# 612_jetracer_esp32c3_030000.net
KiCad netlist of a schematic drawn in EAGLE
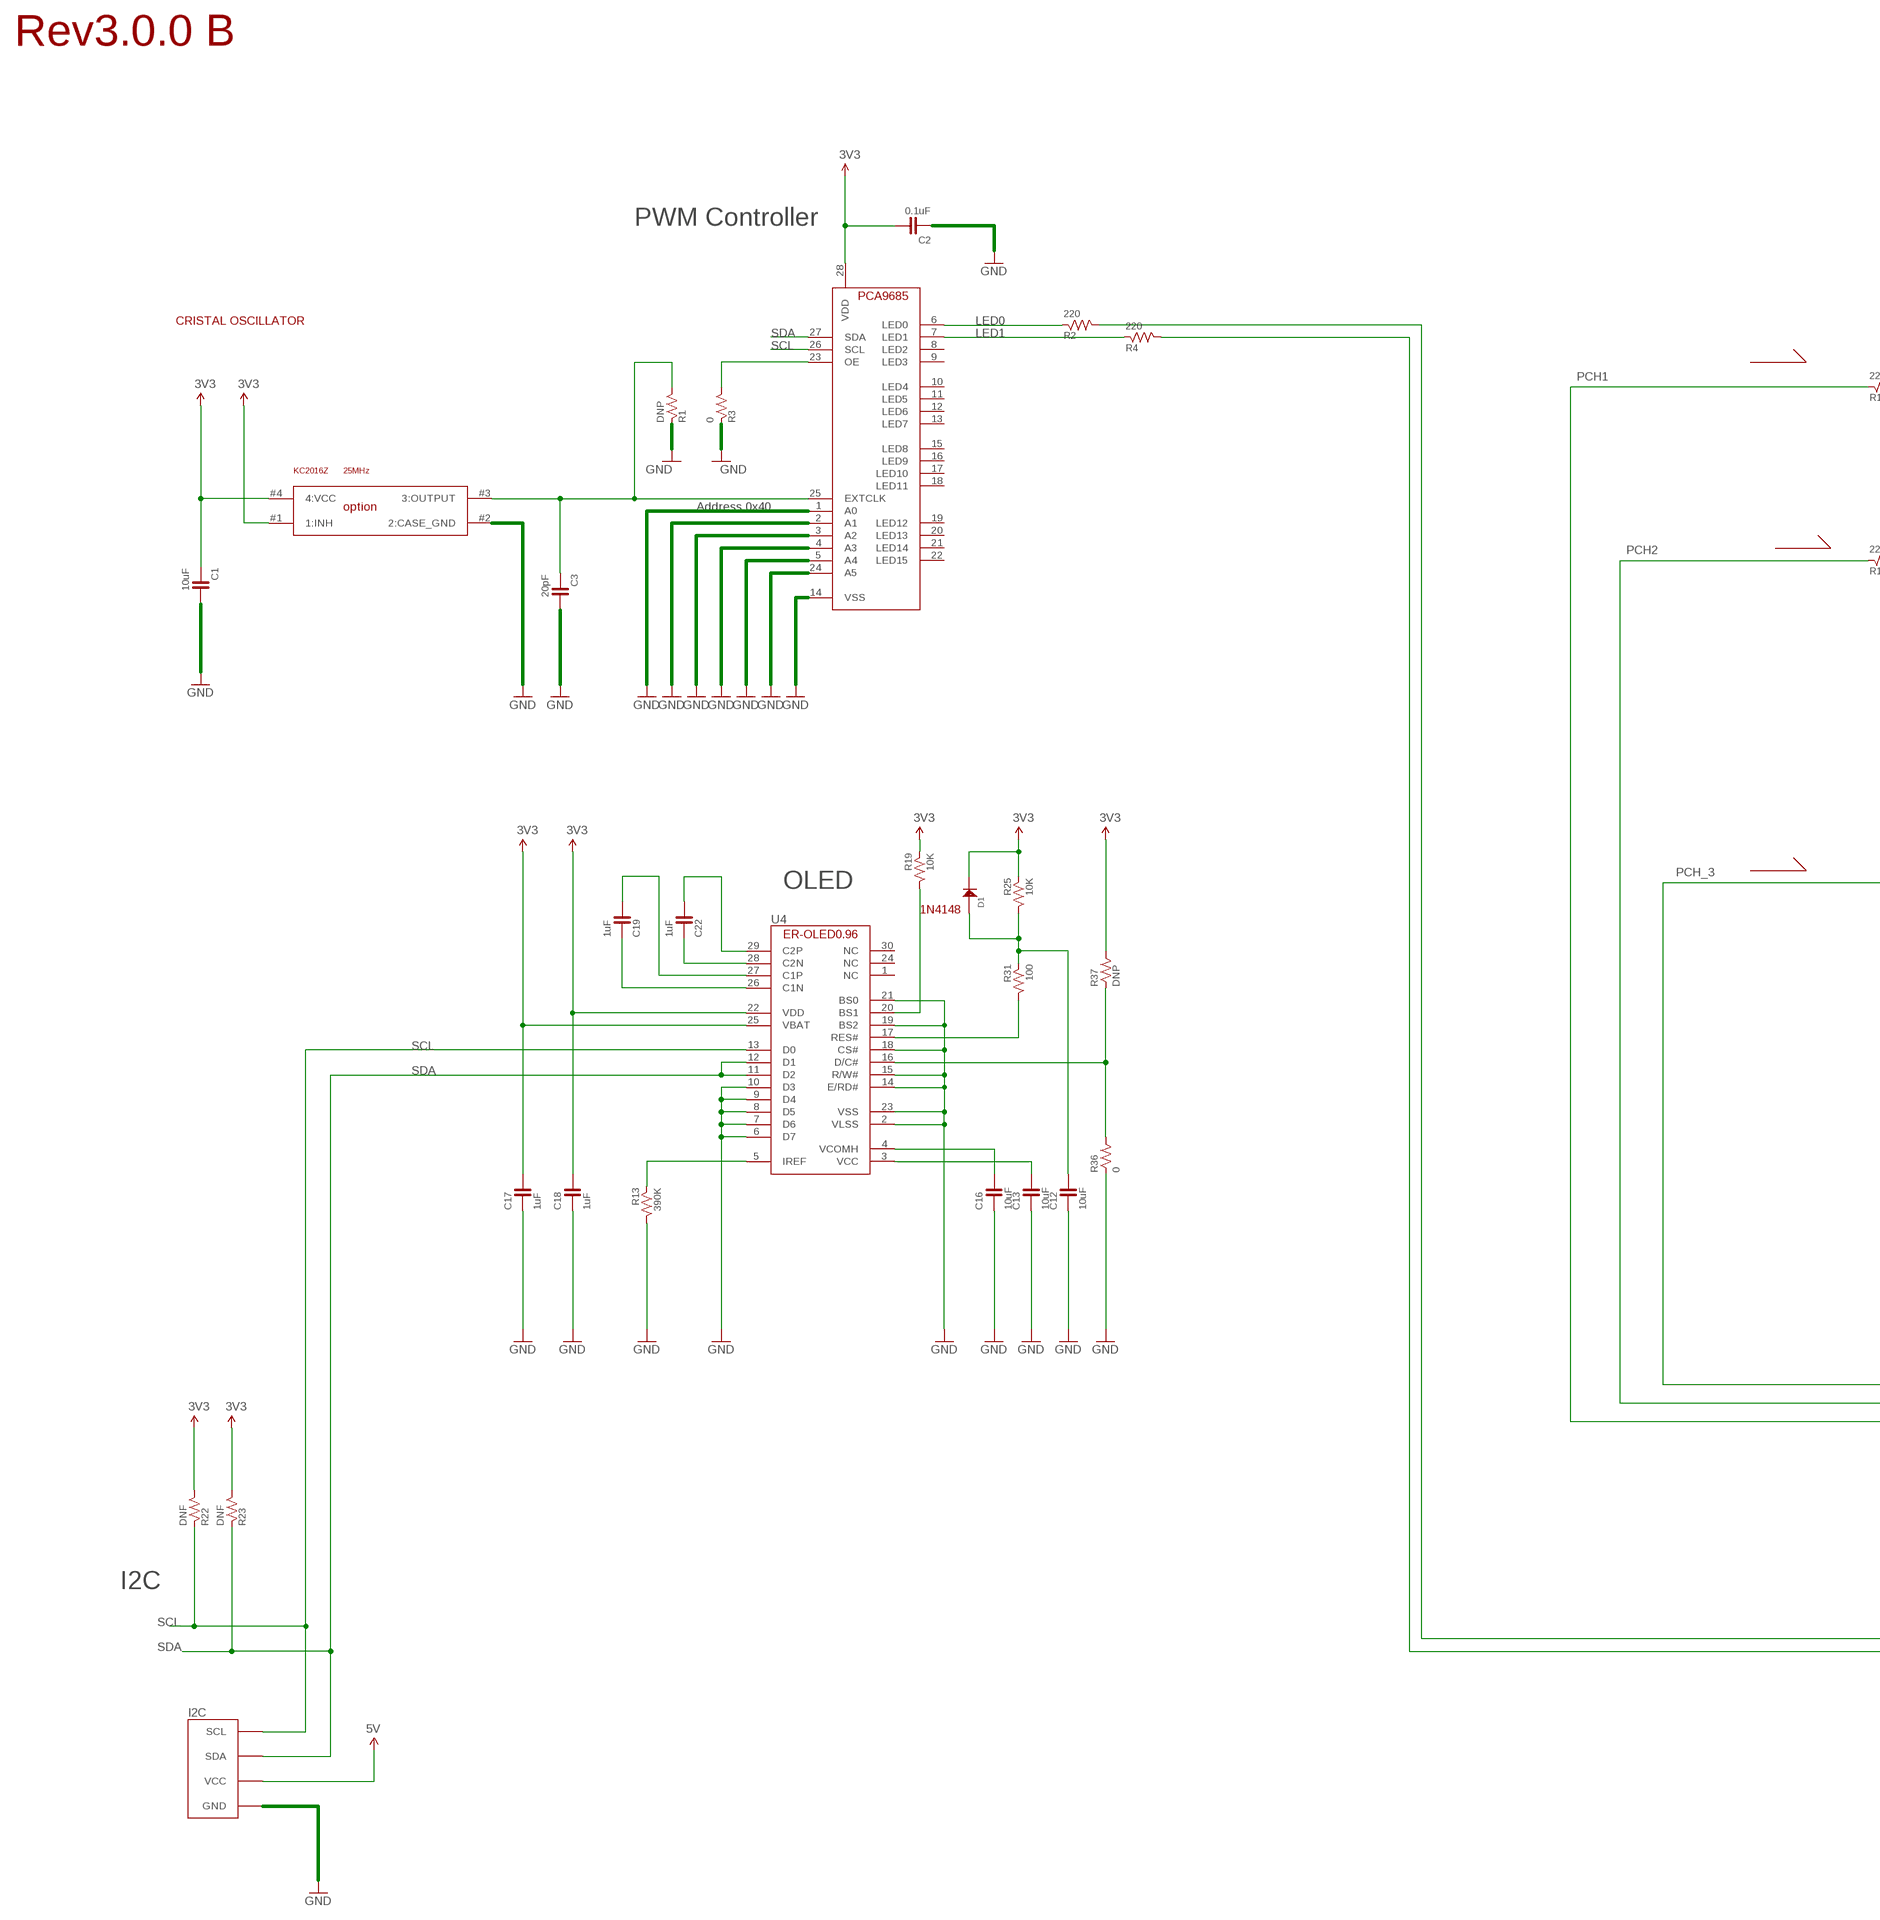
[diagram p0: schematic, sheet 1, part 1 of 3]
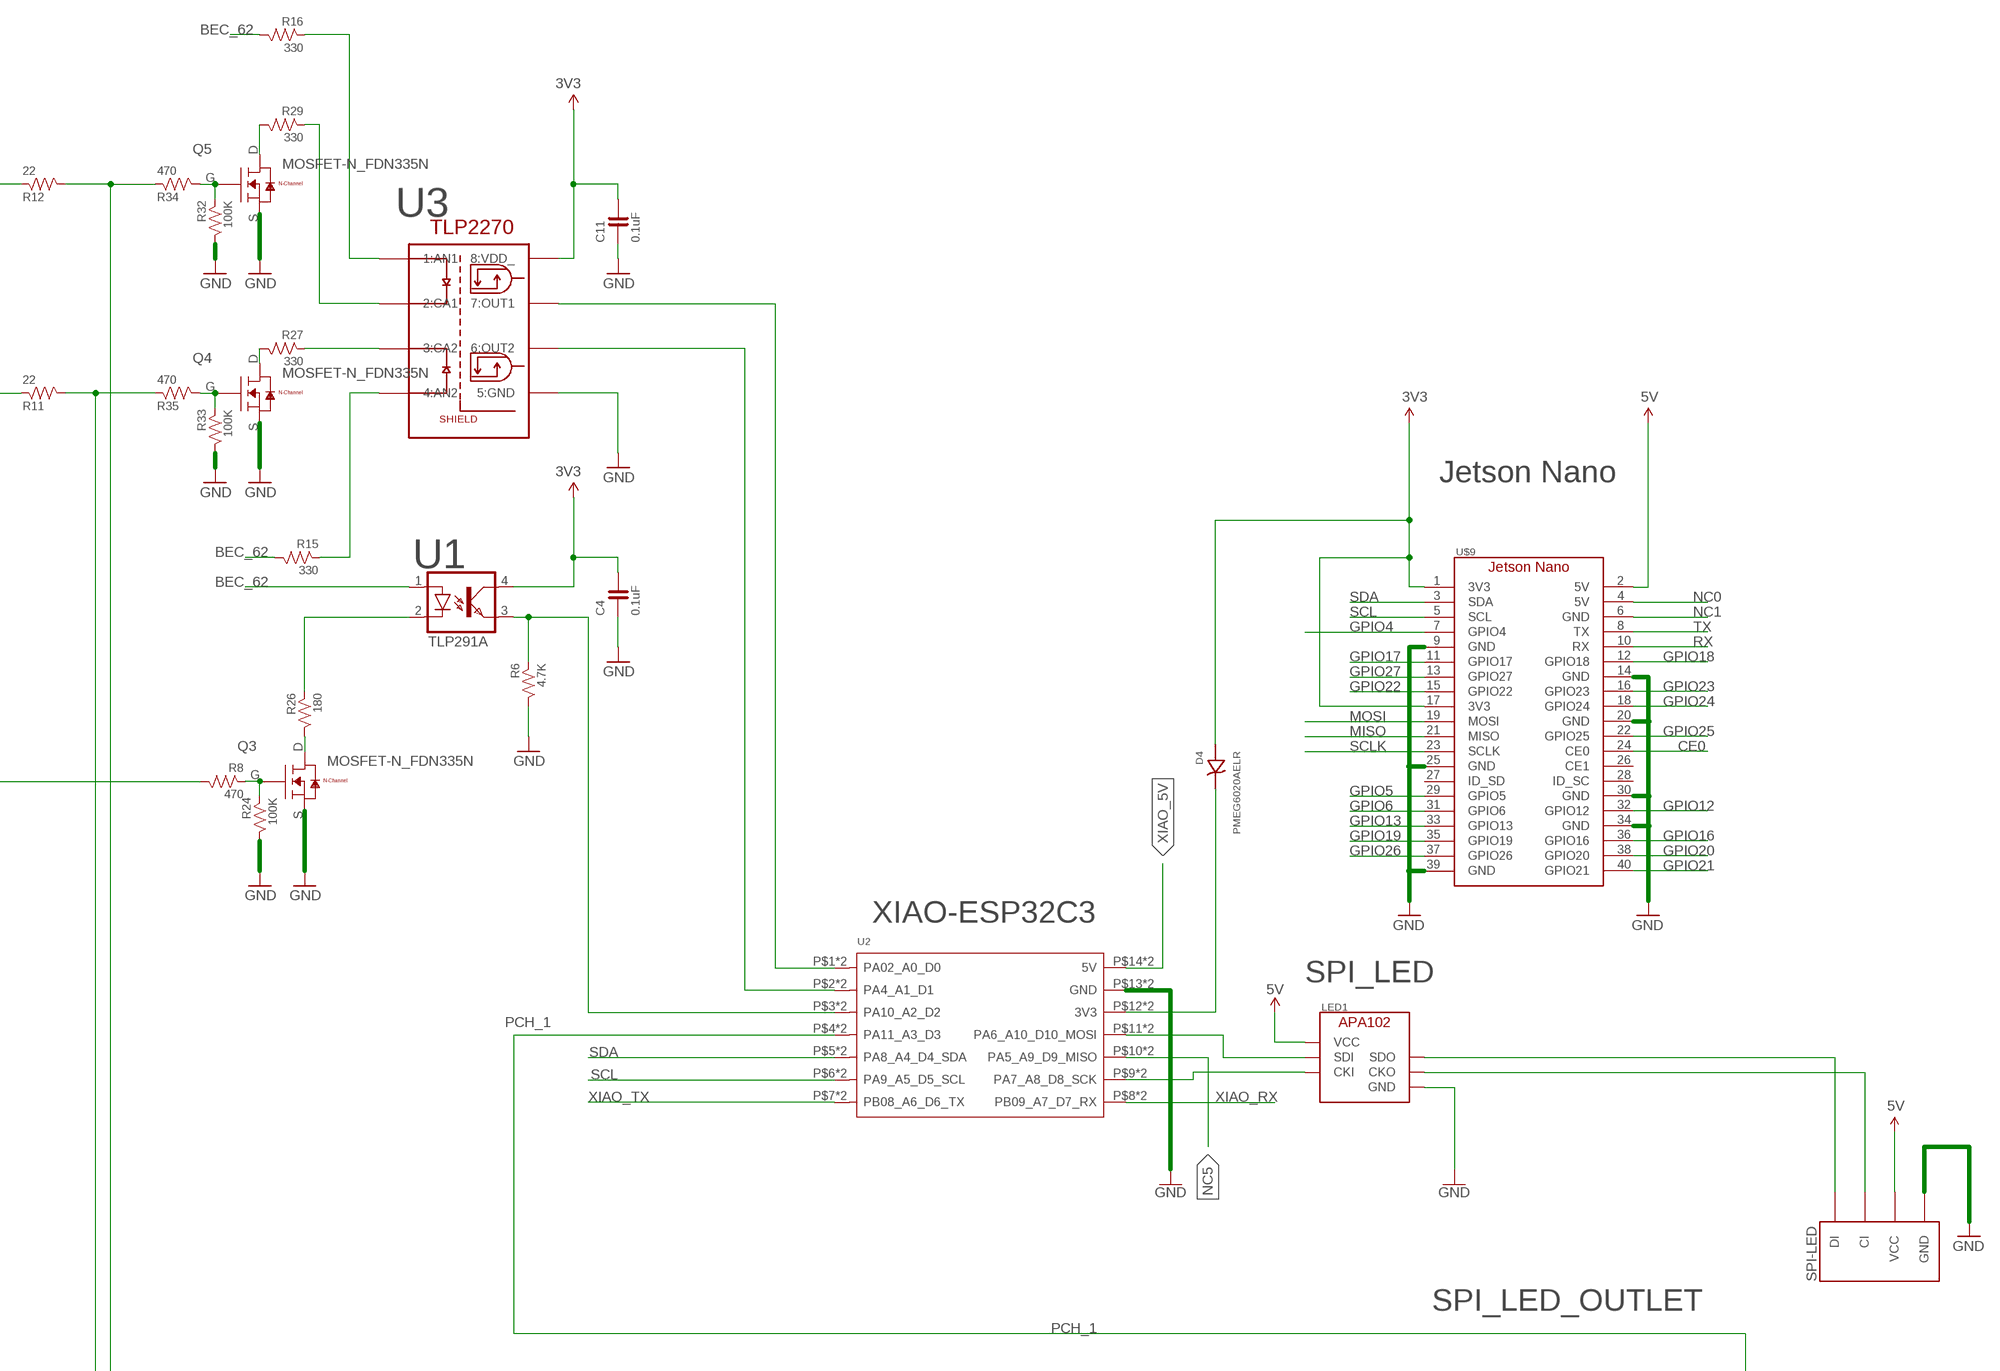
[diagram p1: schematic, sheet 1, part 2 of 3]
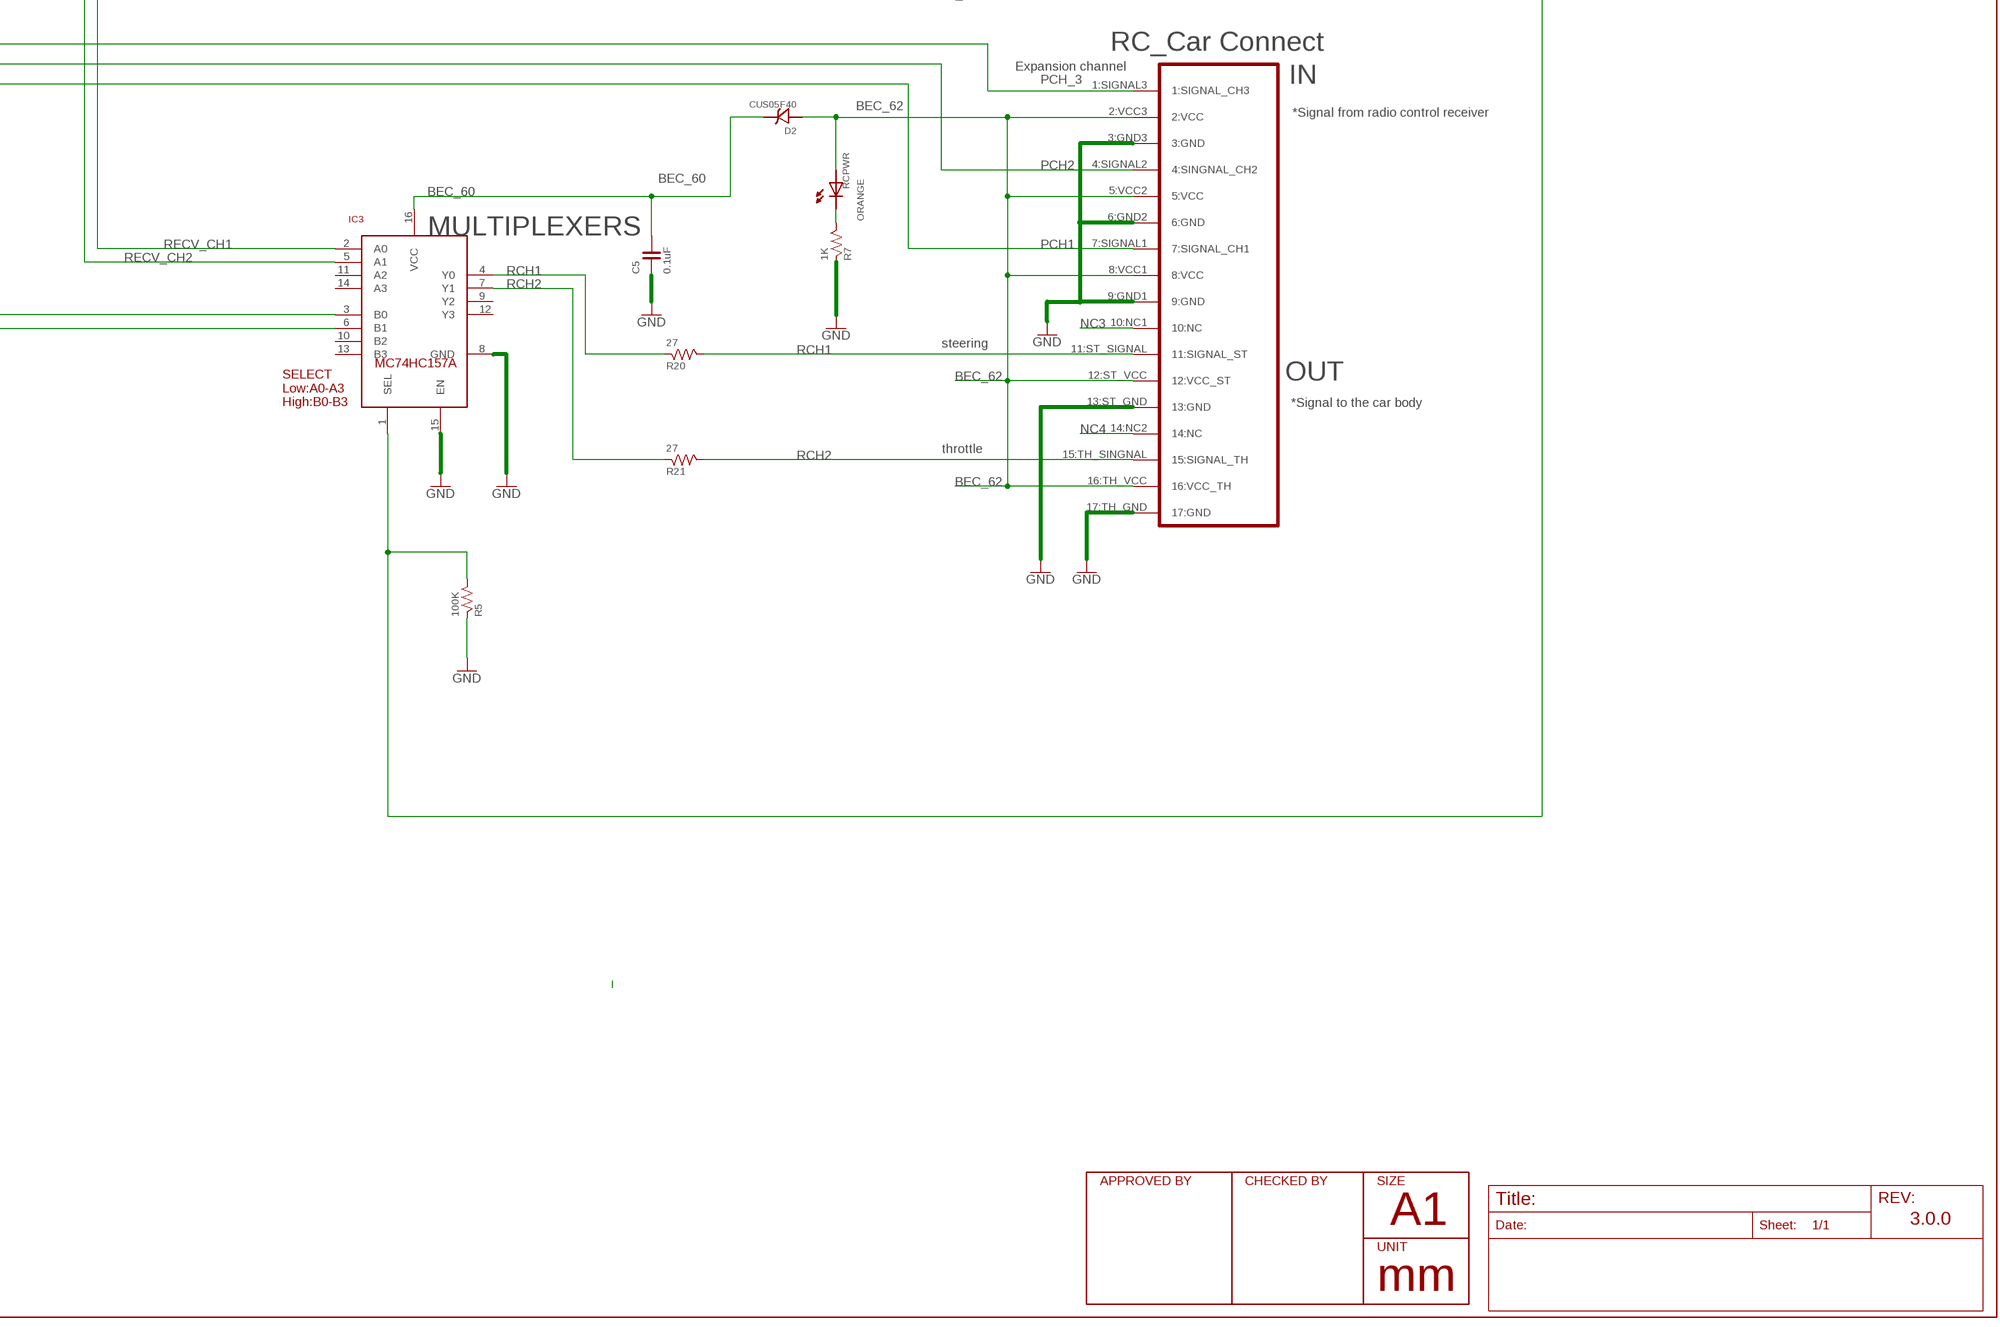
[diagram p2: schematic, sheet 1, part 3 of 3]

(export (version "E")
  (design (tool "Eeschema 10.0.6"))
  (components
    (comp (ref "C1")
      (value "10uF")
      (footprint "eagle-import:0603")
      (libsource (lib "eagle-import") (part "CAPACITOR-0603"))
    )
    (comp (ref "C2")
      (value "0.1uF")
      (footprint "eagle-import:0603")
      (libsource (lib "eagle-import") (part "CAPACITOR-0603"))
    )
    (comp (ref "C3")
      (value "20pF")
      (footprint "eagle-import:0603")
      (libsource (lib "eagle-import") (part "CAPACITOR-0603"))
    )
    (comp (ref "C4")
      (value "0.1uF")
      (footprint "eagle-import:0603")
      (libsource (lib "eagle-import") (part "CAPACITOR-0603"))
    )
    (comp (ref "C5")
      (value "0.1uF")
      (footprint "eagle-import:0603")
      (libsource (lib "eagle-import") (part "CAPACITOR-0603"))
    )
    (comp (ref "C11")
      (value "0.1uF")
      (footprint "eagle-import:0603")
      (libsource (lib "eagle-import") (part "CAPACITOR-0603"))
    )
    (comp (ref "C12")
      (value "10uF")
      (footprint "eagle-import:0603")
      (libsource (lib "eagle-import") (part "CAPACITOR-0603"))
    )
    (comp (ref "C13")
      (value "10uF")
      (footprint "eagle-import:0603")
      (libsource (lib "eagle-import") (part "CAPACITOR-0603"))
    )
    (comp (ref "C16")
      (value "10uF")
      (footprint "eagle-import:0603")
      (libsource (lib "eagle-import") (part "CAPACITOR-0603"))
    )
    (comp (ref "C17")
      (value "1uF")
      (footprint "eagle-import:0603")
      (libsource (lib "eagle-import") (part "CAPACITOR-0603"))
    )
    (comp (ref "C18")
      (value "1uF")
      (footprint "eagle-import:0603")
      (libsource (lib "eagle-import") (part "CAPACITOR-0603"))
    )
    (comp (ref "C19")
      (value "1uF")
      (footprint "eagle-import:0603")
      (libsource (lib "eagle-import") (part "CAPACITOR-0603"))
    )
    (comp (ref "C22")
      (value "1uF")
      (footprint "eagle-import:0603")
      (libsource (lib "eagle-import") (part "CAPACITOR-0603"))
    )
    (comp (ref "D1")
      (value "1N4148")
      (footprint "eagle-import:1N4148W")
      (libsource (lib "eagle-import") (part "1N4148"))
    )
    (comp (ref "D2")
      (value "CUS05F40")
      (footprint "eagle-import:CUS05F40")
      (libsource (lib "eagle-import") (part "CUS05F40"))
    )
    (comp (ref "D4")
      (value "PMEG6020AELR")
      (footprint "eagle-import:SOD123W")
      (libsource (lib "eagle-import") (part "PMEG6020AELR"))
    )
    (comp (ref "I2C")
      (value "FABO-I2C")
      (footprint "eagle-import:I2C-SM04B-PASS-1-FL")
      (libsource (lib "eagle-import") (part "FABO-I2C"))
    )
    (comp (ref "IC3")
      (value "MULTIPLEXERSMC74HC157A")
      (footprint "eagle-import:TSSOP-16")
      (libsource (lib "eagle-import") (part "MULTIPLEXERSMC74HC157A"))
    )
    (comp (ref "IC4")
      (value "PCA9685_BOTTOM")
      (footprint "eagle-import:PCA9685_BOTTOM")
      (libsource (lib "eagle-import") (part "PCA9685_BOTTOM"))
    )
    (comp (ref "LED1")
      (value "APA102_IPIXEL")
      (footprint "eagle-import:APA102_2020")
      (libsource (lib "eagle-import") (part "APA102_IPIXEL"))
    )
    (comp (ref "Q3")
      (value "MOSFET-N_FDN335N")
      (footprint "eagle-import:SUPERSOT-3")
      (libsource (lib "eagle-import") (part "MOSFET-N_FDN335N"))
    )
    (comp (ref "Q4")
      (value "MOSFET-N_FDN335N")
      (footprint "eagle-import:SUPERSOT-3")
      (libsource (lib "eagle-import") (part "MOSFET-N_FDN335N"))
    )
    (comp (ref "Q5")
      (value "MOSFET-N_FDN335N")
      (footprint "eagle-import:SUPERSOT-3")
      (libsource (lib "eagle-import") (part "MOSFET-N_FDN335N"))
    )
    (comp (ref "R1")
      (value "DNP")
      (footprint "eagle-import:0603")
      (libsource (lib "eagle-import") (part "RESISTOR-0603"))
    )
    (comp (ref "R2")
      (value "220")
      (footprint "eagle-import:0603")
      (libsource (lib "eagle-import") (part "RESISTOR-0603"))
    )
    (comp (ref "R3")
      (value "0")
      (footprint "eagle-import:0603")
      (libsource (lib "eagle-import") (part "RESISTOR-0603"))
    )
    (comp (ref "R4")
      (value "220")
      (footprint "eagle-import:0603")
      (libsource (lib "eagle-import") (part "RESISTOR-0603"))
    )
    (comp (ref "R5")
      (value "100K")
      (footprint "eagle-import:0603")
      (libsource (lib "eagle-import") (part "RESISTOR-0603"))
    )
    (comp (ref "R6")
      (value "4.7K")
      (footprint "eagle-import:0603")
      (libsource (lib "eagle-import") (part "RESISTOR-0603"))
    )
    (comp (ref "R7")
      (value "1K")
      (footprint "eagle-import:0603")
      (libsource (lib "eagle-import") (part "RESISTOR-0603"))
    )
    (comp (ref "R8")
      (value "470")
      (footprint "eagle-import:0603")
      (libsource (lib "eagle-import") (part "RESISTOR-0603"))
    )
    (comp (ref "R11")
      (value "22")
      (footprint "eagle-import:0603")
      (libsource (lib "eagle-import") (part "RESISTOR-0603"))
    )
    (comp (ref "R12")
      (value "22")
      (footprint "eagle-import:0603")
      (libsource (lib "eagle-import") (part "RESISTOR-0603"))
    )
    (comp (ref "R13")
      (value "390K")
      (footprint "eagle-import:0603")
      (libsource (lib "eagle-import") (part "RESISTOR-0603"))
    )
    (comp (ref "R15")
      (value "330")
      (footprint "eagle-import:0603")
      (libsource (lib "eagle-import") (part "RESISTOR-0603"))
    )
    (comp (ref "R16")
      (value "330")
      (footprint "eagle-import:0603")
      (libsource (lib "eagle-import") (part "RESISTOR-0603"))
    )
    (comp (ref "R19")
      (value "10K")
      (footprint "eagle-import:0603")
      (libsource (lib "eagle-import") (part "RESISTOR-0603"))
    )
    (comp (ref "R20")
      (value "27")
      (footprint "eagle-import:0603")
      (libsource (lib "eagle-import") (part "RESISTOR-0603"))
    )
    (comp (ref "R21")
      (value "27")
      (footprint "eagle-import:0603")
      (libsource (lib "eagle-import") (part "RESISTOR-0603"))
    )
    (comp (ref "R22")
      (value "DNF")
      (footprint "eagle-import:0603")
      (libsource (lib "eagle-import") (part "RESISTOR-0603"))
    )
    (comp (ref "R23")
      (value "DNF")
      (footprint "eagle-import:0603")
      (libsource (lib "eagle-import") (part "RESISTOR-0603"))
    )
    (comp (ref "R24")
      (value "100K")
      (footprint "eagle-import:0603")
      (libsource (lib "eagle-import") (part "RESISTOR-0603"))
    )
    (comp (ref "R25")
      (value "10K")
      (footprint "eagle-import:0603")
      (libsource (lib "eagle-import") (part "RESISTOR-0603"))
    )
    (comp (ref "R26")
      (value "180")
      (footprint "eagle-import:0603")
      (libsource (lib "eagle-import") (part "RESISTOR-0603"))
    )
    (comp (ref "R27")
      (value "330")
      (footprint "eagle-import:0603")
      (libsource (lib "eagle-import") (part "RESISTOR-0603"))
    )
    (comp (ref "R29")
      (value "330")
      (footprint "eagle-import:0603")
      (libsource (lib "eagle-import") (part "RESISTOR-0603"))
    )
    (comp (ref "R31")
      (value "100")
      (footprint "eagle-import:0603")
      (libsource (lib "eagle-import") (part "RESISTOR-0603"))
    )
    (comp (ref "R32")
      (value "100K")
      (footprint "eagle-import:0603")
      (libsource (lib "eagle-import") (part "RESISTOR-0603"))
    )
    (comp (ref "R33")
      (value "100K")
      (footprint "eagle-import:0603")
      (libsource (lib "eagle-import") (part "RESISTOR-0603"))
    )
    (comp (ref "R34")
      (value "470")
      (footprint "eagle-import:0603")
      (libsource (lib "eagle-import") (part "RESISTOR-0603"))
    )
    (comp (ref "R35")
      (value "470")
      (footprint "eagle-import:0603")
      (libsource (lib "eagle-import") (part "RESISTOR-0603"))
    )
    (comp (ref "R36")
      (value "0")
      (footprint "eagle-import:0805")
      (libsource (lib "eagle-import") (part "RESISTOR-0805"))
    )
    (comp (ref "R37")
      (value "DNP")
      (footprint "eagle-import:0805")
      (fields (field (name "SPICEPREFIX") "R"))
      (libsource (lib "eagle-import") (part "RESISTOR-0805"))
    )
    (comp (ref "RCPWR")
      (value "ORANGE")
      (footprint "eagle-import:0603")
      (libsource (lib "eagle-import") (part "LED-0603"))
    )
    (comp (ref "SPI-LED")
      (value "FABO-SPI-LED")
      (footprint "eagle-import:SPI-SM04B-PASS-1-FL")
      (libsource (lib "eagle-import") (part "FABO-SPI-LED"))
    )
    (comp (ref "U$1")
      (value "RC_17PIN_OUTIN")
      (footprint "eagle-import:PNHEADER_2.54_SMT_17PIN_RC_TT01_02")
      (libsource (lib "eagle-import") (part "RC_17PIN_OUTIN"))
    )
    (comp (ref "U$9")
      (value "JETSON_NANOJETSON_NANO_OVERALL")
      (footprint "eagle-import:JETSON_NANO_DEMENTION")
      (libsource (lib "eagle-import") (part "JETSON_NANOJETSON_NANO_OVERALL"))
    )
    (comp (ref "U$11")
      (value "KC2016Z")
      (footprint "eagle-import:KC2016Z")
      (libsource (lib "eagle-import") (part "KC2016Z"))
    )
    (comp (ref "U1")
      (value "TLP291A")
      (footprint "eagle-import:11-3C1")
      (libsource (lib "eagle-import") (part "TLP291A"))
    )
    (comp (ref "U2")
      (value "MOUDLE-SEEEDUINO-XIAO-ESP32C3")
      (footprint "eagle-import:MOUDLE14P-DIP")
      (libsource (lib "eagle-import") (part "MOUDLE-SEEEDUINO-XIAO-ESP32C3"))
    )
    (comp (ref "U3")
      (value "TLP2270")
      (footprint "eagle-import:TLP2270")
      (libsource (lib "eagle-import") (part "TLP2270"))
    )
    (comp (ref "U4")
      (value "ER-OLED0.96-1ER-CON30HT-1")
      (footprint "eagle-import:ER-CON30HT-1")
      (libsource (lib "eagle-import") (part "ER-OLED0.96-1ER-CON30HT-1"))
    )
  )
  (nets
    (net (code "1") (name "/BEC_60") (class "Default")
      (node (ref "C5") (pin "2") (pinfunction "2_2") (pintype "passive"))
      (node (ref "D2") (pin "C") (pinfunction "CATHODE_C") (pintype "bidirectional"))
      (node (ref "IC3") (pin "16") (pinfunction "VCC_16") (pintype "bidirectional"))
    )
    (net (code "2") (name "/BEC_62") (class "Default")
      (node (ref "D2") (pin "A") (pinfunction "ANODE_A") (pintype "bidirectional"))
      (node (ref "R15") (pin "2") (pinfunction "2_2") (pintype "bidirectional"))
      (node (ref "R16") (pin "2") (pinfunction "2_2") (pintype "bidirectional"))
      (node (ref "RCPWR") (pin "ANODE") (pinfunction "ANODE_ANODE") (pintype "passive"))
      (node (ref "U$1") (pin "12:ST_VCC") (pinfunction "12:VCC_ST_12:ST_VCC") (pintype "bidirectional"))
      (node (ref "U$1") (pin "16:TH_VCC") (pinfunction "16:VCC_TH_16:TH_VCC") (pintype "bidirectional"))
      (node (ref "U$1") (pin "2:VCC3") (pinfunction "2:VCC_2:VCC3") (pintype "bidirectional"))
      (node (ref "U$1") (pin "5:VCC2") (pinfunction "5:VCC_5:VCC2") (pintype "bidirectional"))
      (node (ref "U$1") (pin "8:VCC1") (pinfunction "8:VCC_8:VCC1") (pintype "bidirectional"))
      (node (ref "U1") (pin "1") (pinfunction "A_1") (pintype "passive"))
    )
    (net (code "3") (name "/CE0") (class "Default")
      (node (ref "U$9") (pin "24") (pinfunction "CE0_24") (pintype "bidirectional"))
    )
    (net (code "4") (name "/GPIO4") (class "Default")
      (node (ref "U$9") (pin "7") (pinfunction "GPIO4_7") (pintype "bidirectional"))
    )
    (net (code "5") (name "/GPIO5") (class "Default")
      (node (ref "U$9") (pin "29") (pinfunction "GPIO5_29") (pintype "bidirectional"))
    )
    (net (code "6") (name "/GPIO6") (class "Default")
      (node (ref "U$9") (pin "31") (pinfunction "GPIO6_31") (pintype "bidirectional"))
    )
    (net (code "7") (name "/GPIO12") (class "Default")
      (node (ref "U$9") (pin "32") (pinfunction "GPIO12_32") (pintype "bidirectional"))
    )
    (net (code "8") (name "/GPIO13") (class "Default")
      (node (ref "U$9") (pin "33") (pinfunction "GPIO13_33") (pintype "bidirectional"))
    )
    (net (code "9") (name "/GPIO16") (class "Default")
      (node (ref "U$9") (pin "36") (pinfunction "GPIO16_36") (pintype "bidirectional"))
    )
    (net (code "10") (name "/GPIO17") (class "Default")
      (node (ref "U$9") (pin "11") (pinfunction "GPIO17_11") (pintype "bidirectional"))
    )
    (net (code "11") (name "/GPIO18") (class "Default")
      (node (ref "U$9") (pin "12") (pinfunction "GPIO18_12") (pintype "bidirectional"))
    )
    (net (code "12") (name "/GPIO19") (class "Default")
      (node (ref "U$9") (pin "35") (pinfunction "GPIO19_35") (pintype "bidirectional"))
    )
    (net (code "13") (name "/GPIO20") (class "Default")
      (node (ref "U$9") (pin "38") (pinfunction "GPIO20_38") (pintype "bidirectional"))
    )
    (net (code "14") (name "/GPIO21") (class "Default")
      (node (ref "U$9") (pin "40") (pinfunction "GPIO21_40") (pintype "bidirectional"))
    )
    (net (code "15") (name "/GPIO22") (class "Default")
      (node (ref "U$9") (pin "15") (pinfunction "GPIO22_15") (pintype "bidirectional"))
    )
    (net (code "16") (name "/GPIO23") (class "Default")
      (node (ref "U$9") (pin "16") (pinfunction "GPIO23_16") (pintype "bidirectional"))
    )
    (net (code "17") (name "/GPIO24") (class "Default")
      (node (ref "U$9") (pin "18") (pinfunction "GPIO24_18") (pintype "bidirectional"))
    )
    (net (code "18") (name "/GPIO25") (class "Default")
      (node (ref "U$9") (pin "22") (pinfunction "GPIO25_22") (pintype "bidirectional"))
    )
    (net (code "19") (name "/GPIO26") (class "Default")
      (node (ref "U$9") (pin "37") (pinfunction "GPIO26_37") (pintype "bidirectional"))
    )
    (net (code "20") (name "/GPIO27") (class "Default")
      (node (ref "U$9") (pin "13") (pinfunction "GPIO27_13") (pintype "bidirectional"))
    )
    (net (code "21") (name "/LED0") (class "Default")
      (node (ref "IC4") (pin "6") (pinfunction "LED0_6") (pintype "bidirectional"))
      (node (ref "R2") (pin "1") (pinfunction "1_1") (pintype "bidirectional"))
    )
    (net (code "22") (name "/LED1") (class "Default")
      (node (ref "IC4") (pin "7") (pinfunction "LED1_7") (pintype "bidirectional"))
      (node (ref "R4") (pin "1") (pinfunction "1_1") (pintype "bidirectional"))
    )
    (net (code "23") (name "/MISO") (class "Default")
      (node (ref "U$9") (pin "21") (pinfunction "MISO_21") (pintype "bidirectional"))
    )
    (net (code "24") (name "/MOSI") (class "Default")
      (node (ref "U$9") (pin "19") (pinfunction "MOSI_19") (pintype "bidirectional"))
    )
    (net (code "25") (name "/NC0") (class "Default")
      (node (ref "U$9") (pin "4") (pinfunction "5V_4") (pintype "bidirectional"))
    )
    (net (code "26") (name "/NC1") (class "Default")
      (node (ref "U$9") (pin "6") (pinfunction "GND_6") (pintype "bidirectional"))
    )
    (net (code "27") (name "/NC3") (class "Default")
      (node (ref "U$1") (pin "10:NC1") (pinfunction "10:NC_10:NC1") (pintype "bidirectional"))
    )
    (net (code "28") (name "/NC4") (class "Default")
      (node (ref "U$1") (pin "14:NC2") (pinfunction "14:NC_14:NC2") (pintype "bidirectional"))
    )
    (net (code "29") (name "/PCH1") (class "Default")
      (node (ref "R12") (pin "1") (pinfunction "1_1") (pintype "bidirectional"))
      (node (ref "U$1") (pin "7:SIGNAL1") (pinfunction "7:SIGNAL_CH1_7:SIGNAL1") (pintype "bidirectional"))
    )
    (net (code "30") (name "/PCH2") (class "Default")
      (node (ref "R11") (pin "1") (pinfunction "1_1") (pintype "bidirectional"))
      (node (ref "U$1") (pin "4:SIGNAL2") (pinfunction "4:SINGNAL_CH2_4:SIGNAL2") (pintype "bidirectional"))
    )
    (net (code "31") (name "/PCH_1") (class "Default")
      (node (ref "IC3") (pin "1") (pinfunction "SEL_1") (pintype "bidirectional"))
      (node (ref "R5") (pin "2") (pinfunction "2_2") (pintype "bidirectional"))
      (node (ref "U2") (pin "P$18") (pinfunction "PA11_A3_D3_P$18") (pintype "bidirectional"))
      (node (ref "U2") (pin "P$4") (pinfunction "PA11_A3_D3_P$4") (pintype "bidirectional"))
    )
    (net (code "32") (name "/PCH_3") (class "Default")
      (node (ref "R8") (pin "2") (pinfunction "2_2") (pintype "bidirectional"))
      (node (ref "U$1") (pin "1:SIGNAL3") (pinfunction "1:SIGNAL_CH3_1:SIGNAL3") (pintype "bidirectional"))
    )
    (net (code "33") (name "/RCH1") (class "Default")
      (node (ref "IC3") (pin "4") (pinfunction "Y0_4") (pintype "bidirectional"))
      (node (ref "R20") (pin "1") (pinfunction "1_1") (pintype "bidirectional"))
    )
    (net (code "34") (name "/RCH2") (class "Default")
      (node (ref "IC3") (pin "7") (pinfunction "Y1_7") (pintype "bidirectional"))
      (node (ref "R21") (pin "1") (pinfunction "1_1") (pintype "bidirectional"))
    )
    (net (code "35") (name "/RECV_CH1") (class "Default")
      (node (ref "IC3") (pin "2") (pinfunction "A0_2") (pintype "bidirectional"))
      (node (ref "R12") (pin "2") (pinfunction "2_2") (pintype "bidirectional"))
      (node (ref "R34") (pin "1") (pinfunction "1_1") (pintype "bidirectional"))
    )
    (net (code "36") (name "/RECV_CH2") (class "Default")
      (node (ref "IC3") (pin "5") (pinfunction "A1_5") (pintype "bidirectional"))
      (node (ref "R11") (pin "2") (pinfunction "2_2") (pintype "bidirectional"))
      (node (ref "R35") (pin "1") (pinfunction "1_1") (pintype "bidirectional"))
    )
    (net (code "37") (name "/RX") (class "Default")
      (node (ref "U$9") (pin "10") (pinfunction "RX_10") (pintype "bidirectional"))
    )
    (net (code "38") (name "/SCL") (class "Default")
      (node (ref "I2C") (pin "SCL") (pinfunction "SCL_SCL") (pintype "bidirectional"))
      (node (ref "IC4") (pin "26") (pinfunction "SCL_26") (pintype "bidirectional"))
      (node (ref "R22") (pin "1") (pinfunction "1_1") (pintype "bidirectional"))
      (node (ref "U$9") (pin "5") (pinfunction "SCL_5") (pintype "bidirectional"))
      (node (ref "U2") (pin "P$20") (pinfunction "PA9_A5_D5_SCL_P$20") (pintype "bidirectional"))
      (node (ref "U2") (pin "P$6") (pinfunction "PA9_A5_D5_SCL_P$6") (pintype "bidirectional"))
      (node (ref "U4") (pin "13") (pinfunction "D0_13") (pintype "bidirectional"))
    )
    (net (code "39") (name "/SCLK") (class "Default")
      (node (ref "U$9") (pin "23") (pinfunction "SCLK_23") (pintype "bidirectional"))
    )
    (net (code "40") (name "/SDA") (class "Default")
      (node (ref "I2C") (pin "SDA") (pinfunction "SDA_SDA") (pintype "bidirectional"))
      (node (ref "IC4") (pin "27") (pinfunction "SDA_27") (pintype "bidirectional"))
      (node (ref "R23") (pin "1") (pinfunction "1_1") (pintype "bidirectional"))
      (node (ref "U$9") (pin "3") (pinfunction "SDA_3") (pintype "bidirectional"))
      (node (ref "U2") (pin "P$19") (pinfunction "PA8_A4_D4_SDA_P$19") (pintype "bidirectional"))
      (node (ref "U2") (pin "P$5") (pinfunction "PA8_A4_D4_SDA_P$5") (pintype "bidirectional"))
      (node (ref "U4") (pin "11") (pinfunction "D2_11") (pintype "bidirectional"))
      (node (ref "U4") (pin "12") (pinfunction "D1_12") (pintype "bidirectional"))
    )
    (net (code "41") (name "/TX") (class "Default")
      (node (ref "U$9") (pin "8") (pinfunction "TX_8") (pintype "bidirectional"))
    )
    (net (code "42") (name "/XIAO_RX") (class "Default")
      (node (ref "U2") (pin "P$22") (pinfunction "PB09_A7_D7_RX_P$22") (pintype "bidirectional"))
      (node (ref "U2") (pin "P$8") (pinfunction "PB09_A7_D7_RX_P$8") (pintype "bidirectional"))
    )
    (net (code "43") (name "/XIAO_TX") (class "Default")
      (node (ref "U2") (pin "P$21") (pinfunction "PB08_A6_D6_TX_P$21") (pintype "bidirectional"))
      (node (ref "U2") (pin "P$7") (pinfunction "PB08_A6_D6_TX_P$7") (pintype "bidirectional"))
    )
    (net (code "44") (name "3V3") (class "Default")
      (node (ref "C1") (pin "1") (pinfunction "1_1") (pintype "passive"))
      (node (ref "C11") (pin "2") (pinfunction "2_2") (pintype "passive"))
      (node (ref "C17") (pin "2") (pinfunction "2_2") (pintype "passive"))
      (node (ref "C18") (pin "2") (pinfunction "2_2") (pintype "passive"))
      (node (ref "C2") (pin "2") (pinfunction "2_2") (pintype "passive"))
      (node (ref "C4") (pin "2") (pinfunction "2_2") (pintype "passive"))
      (node (ref "D1") (pin "CATHODE") (pinfunction "CATHODE_CATHODE") (pintype "bidirectional"))
      (node (ref "D4") (pin "2") (pinfunction "ANODE_2") (pintype "bidirectional"))
      (node (ref "IC4") (pin "28") (pinfunction "VDD_28") (pintype "bidirectional"))
      (node (ref "R19") (pin "1") (pinfunction "1_1") (pintype "bidirectional"))
      (node (ref "R22") (pin "2") (pinfunction "2_2") (pintype "bidirectional"))
      (node (ref "R23") (pin "2") (pinfunction "2_2") (pintype "bidirectional"))
      (node (ref "R25") (pin "1") (pinfunction "1_1") (pintype "bidirectional"))
      (node (ref "R37") (pin "2") (pinfunction "2_2") (pintype "bidirectional"))
      (node (ref "U$11") (pin "#1") (pinfunction "1:INH_#1") (pintype "bidirectional"))
      (node (ref "U$11") (pin "#4") (pinfunction "4:VCC_#4") (pintype "bidirectional"))
      (node (ref "U$9") (pin "1") (pinfunction "3V3_1") (pintype "bidirectional"))
      (node (ref "U$9") (pin "17") (pinfunction "3V3_17") (pintype "bidirectional"))
      (node (ref "U1") (pin "4") (pinfunction "COL_4") (pintype "passive"))
      (node (ref "U3") (pin "8") (pinfunction "8:VDD__8") (pintype "bidirectional"))
      (node (ref "U4") (pin "22") (pinfunction "VDD_22") (pintype "bidirectional"))
      (node (ref "U4") (pin "25") (pinfunction "VBAT_25") (pintype "bidirectional"))
    )
    (net (code "45") (name "5V") (class "Default")
      (node (ref "I2C") (pin "5V") (pinfunction "VCC_5V") (pintype "bidirectional"))
      (node (ref "LED1") (pin "VCC") (pinfunction "VCC_VCC") (pintype "bidirectional"))
      (node (ref "SPI-LED") (pin "5V") (pinfunction "VCC_5V") (pintype "bidirectional"))
      (node (ref "U$9") (pin "2") (pinfunction "5V_2") (pintype "bidirectional"))
    )
    (net (code "46") (name "GND") (class "Default")
      (node (ref "C1") (pin "2") (pinfunction "2_2") (pintype "passive"))
      (node (ref "C11") (pin "1") (pinfunction "1_1") (pintype "passive"))
      (node (ref "C12") (pin "1") (pinfunction "1_1") (pintype "passive"))
      (node (ref "C13") (pin "1") (pinfunction "1_1") (pintype "passive"))
      (node (ref "C16") (pin "1") (pinfunction "1_1") (pintype "passive"))
      (node (ref "C17") (pin "1") (pinfunction "1_1") (pintype "passive"))
      (node (ref "C18") (pin "1") (pinfunction "1_1") (pintype "passive"))
      (node (ref "C2") (pin "1") (pinfunction "1_1") (pintype "passive"))
      (node (ref "C3") (pin "2") (pinfunction "2_2") (pintype "passive"))
      (node (ref "C4") (pin "1") (pinfunction "1_1") (pintype "passive"))
      (node (ref "C5") (pin "1") (pinfunction "1_1") (pintype "passive"))
      (node (ref "I2C") (pin "GND") (pinfunction "GND_GND") (pintype "bidirectional"))
      (node (ref "IC3") (pin "15") (pinfunction "EN_15") (pintype "bidirectional"))
      (node (ref "IC3") (pin "8") (pinfunction "GND_8") (pintype "bidirectional"))
      (node (ref "IC4") (pin "1") (pinfunction "A0_1") (pintype "bidirectional"))
      (node (ref "IC4") (pin "14") (pinfunction "VSS_14") (pintype "bidirectional"))
      (node (ref "IC4") (pin "2") (pinfunction "A1_2") (pintype "bidirectional"))
      (node (ref "IC4") (pin "24") (pinfunction "A5_24") (pintype "bidirectional"))
      (node (ref "IC4") (pin "3") (pinfunction "A2_3") (pintype "bidirectional"))
      (node (ref "IC4") (pin "4") (pinfunction "A3_4") (pintype "bidirectional"))
      (node (ref "IC4") (pin "5") (pinfunction "A4_5") (pintype "bidirectional"))
      (node (ref "LED1") (pin "GND") (pinfunction "GND_GND") (pintype "bidirectional"))
      (node (ref "Q3") (pin "S") (pinfunction "S_S") (pintype "passive"))
      (node (ref "Q4") (pin "S") (pinfunction "S_S") (pintype "passive"))
      (node (ref "Q5") (pin "S") (pinfunction "S_S") (pintype "passive"))
      (node (ref "R1") (pin "1") (pinfunction "1_1") (pintype "bidirectional"))
      (node (ref "R13") (pin "2") (pinfunction "2_2") (pintype "bidirectional"))
      (node (ref "R24") (pin "2") (pinfunction "2_2") (pintype "bidirectional"))
      (node (ref "R3") (pin "1") (pinfunction "1_1") (pintype "bidirectional"))
      (node (ref "R32") (pin "2") (pinfunction "2_2") (pintype "bidirectional"))
      (node (ref "R33") (pin "2") (pinfunction "2_2") (pintype "bidirectional"))
      (node (ref "R36") (pin "1") (pinfunction "1_1") (pintype "bidirectional"))
      (node (ref "R5") (pin "1") (pinfunction "1_1") (pintype "bidirectional"))
      (node (ref "R6") (pin "2") (pinfunction "2_2") (pintype "bidirectional"))
      (node (ref "R7") (pin "1") (pinfunction "1_1") (pintype "bidirectional"))
      (node (ref "SPI-LED") (pin "GND") (pinfunction "GND_GND") (pintype "bidirectional"))
      (node (ref "U$1") (pin "13:ST_GND") (pinfunction "13:GND_13:ST_GND") (pintype "bidirectional"))
      (node (ref "U$1") (pin "17:TH_GND") (pinfunction "17:GND_17:TH_GND") (pintype "bidirectional"))
      (node (ref "U$1") (pin "3:GND3") (pinfunction "3:GND_3:GND3") (pintype "bidirectional"))
      (node (ref "U$1") (pin "6:GND2") (pinfunction "6:GND_6:GND2") (pintype "bidirectional"))
      (node (ref "U$1") (pin "9:GND1") (pinfunction "9:GND_9:GND1") (pintype "bidirectional"))
      (node (ref "U$11") (pin "#2") (pinfunction "2:CASE_GND_#2") (pintype "bidirectional"))
      (node (ref "U$9") (pin "14") (pinfunction "GND_14") (pintype "bidirectional"))
      (node (ref "U$9") (pin "20") (pinfunction "GND_20") (pintype "bidirectional"))
      (node (ref "U$9") (pin "25") (pinfunction "GND_25") (pintype "bidirectional"))
      (node (ref "U$9") (pin "30") (pinfunction "GND_30") (pintype "bidirectional"))
      (node (ref "U$9") (pin "34") (pinfunction "GND_34") (pintype "bidirectional"))
      (node (ref "U$9") (pin "39") (pinfunction "GND_39") (pintype "bidirectional"))
      (node (ref "U$9") (pin "9") (pinfunction "GND_9") (pintype "bidirectional"))
      (node (ref "U2") (pin "P$13") (pinfunction "GND_P$13") (pintype "bidirectional"))
      (node (ref "U2") (pin "P$27") (pinfunction "GND_P$27") (pintype "bidirectional"))
      (node (ref "U3") (pin "5") (pinfunction "5:GND_5") (pintype "bidirectional"))
      (node (ref "U4") (pin "10") (pinfunction "D3_10") (pintype "bidirectional"))
      (node (ref "U4") (pin "14") (pinfunction "E/RD#_14") (pintype "bidirectional"))
      (node (ref "U4") (pin "15") (pinfunction "R/W#_15") (pintype "bidirectional"))
      (node (ref "U4") (pin "18") (pinfunction "CS#_18") (pintype "bidirectional"))
      (node (ref "U4") (pin "19") (pinfunction "BS2_19") (pintype "bidirectional"))
      (node (ref "U4") (pin "2") (pinfunction "VLSS_2") (pintype "bidirectional"))
      (node (ref "U4") (pin "21") (pinfunction "BS0_21") (pintype "bidirectional"))
      (node (ref "U4") (pin "23") (pinfunction "VSS_23") (pintype "bidirectional"))
      (node (ref "U4") (pin "6") (pinfunction "D7_6") (pintype "bidirectional"))
      (node (ref "U4") (pin "7") (pinfunction "D6_7") (pintype "bidirectional"))
      (node (ref "U4") (pin "8") (pinfunction "D5_8") (pintype "bidirectional"))
      (node (ref "U4") (pin "9") (pinfunction "D4_9") (pintype "bidirectional"))
    )
    (net (code "47") (name "NC5") (class "Default")
      (node (ref "U2") (pin "P$10") (pinfunction "PA5_A9_D9_MISO_P$10") (pintype "bidirectional"))
      (node (ref "U2") (pin "P$24") (pinfunction "PA5_A9_D9_MISO_P$24") (pintype "bidirectional"))
    )
    (net (code "48") (name "Net-(C12-Pad2)") (class "Default")
      (node (ref "C12") (pin "2") (pinfunction "2_2") (pintype "passive"))
      (node (ref "D1") (pin "ANODE") (pinfunction "ANODE_ANODE") (pintype "bidirectional"))
      (node (ref "R25") (pin "2") (pinfunction "2_2") (pintype "bidirectional"))
      (node (ref "R31") (pin "1") (pinfunction "1_1") (pintype "bidirectional"))
    )
    (net (code "49") (name "Net-(D4-CATHODE)") (class "Default")
      (node (ref "D4") (pin "1") (pinfunction "CATHODE_1") (pintype "bidirectional"))
      (node (ref "U2") (pin "P$12") (pinfunction "3V3_P$12") (pintype "bidirectional"))
      (node (ref "U2") (pin "P$26") (pinfunction "3V3_P$26") (pintype "bidirectional"))
    )
    (net (code "50") (name "Net-(IC3-B0)") (class "Default")
      (node (ref "IC3") (pin "3") (pinfunction "B0_3") (pintype "bidirectional"))
      (node (ref "R2") (pin "2") (pinfunction "2_2") (pintype "bidirectional"))
    )
    (net (code "51") (name "Net-(IC3-B1)") (class "Default")
      (node (ref "IC3") (pin "6") (pinfunction "B1_6") (pintype "bidirectional"))
      (node (ref "R4") (pin "2") (pinfunction "2_2") (pintype "bidirectional"))
    )
    (net (code "52") (name "Net-(IC4-EXTCLK)") (class "Default")
      (node (ref "C3") (pin "1") (pinfunction "1_1") (pintype "passive"))
      (node (ref "IC4") (pin "25") (pinfunction "EXTCLK_25") (pintype "bidirectional"))
      (node (ref "R1") (pin "2") (pinfunction "2_2") (pintype "bidirectional"))
      (node (ref "U$11") (pin "#3") (pinfunction "3:OUTPUT_#3") (pintype "bidirectional"))
    )
    (net (code "53") (name "Net-(IC4-OE)") (class "Default")
      (node (ref "IC4") (pin "23") (pinfunction "OE_23") (pintype "bidirectional"))
      (node (ref "R3") (pin "2") (pinfunction "2_2") (pintype "bidirectional"))
    )
    (net (code "54") (name "Net-(LED1-PadCKI)") (class "Default")
      (node (ref "LED1") (pin "CKI") (pinfunction "CKI_CKI") (pintype "bidirectional"))
      (node (ref "U2") (pin "P$23") (pinfunction "PA7_A8_D8_SCK_P$23") (pintype "bidirectional"))
      (node (ref "U2") (pin "P$9") (pinfunction "PA7_A8_D8_SCK_P$9") (pintype "bidirectional"))
    )
    (net (code "55") (name "Net-(LED1-PadCKO)") (class "Default")
      (node (ref "LED1") (pin "CKO") (pinfunction "CKO_CKO") (pintype "bidirectional"))
      (node (ref "SPI-LED") (pin "CI") (pinfunction "CI_CI") (pintype "bidirectional"))
    )
    (net (code "56") (name "Net-(LED1-PadSDI)") (class "Default")
      (node (ref "LED1") (pin "SDI") (pinfunction "SDI_SDI") (pintype "bidirectional"))
      (node (ref "U2") (pin "P$11") (pinfunction "PA6_A10_D10_MOSI_P$11") (pintype "bidirectional"))
      (node (ref "U2") (pin "P$25") (pinfunction "PA6_A10_D10_MOSI_P$25") (pintype "bidirectional"))
    )
    (net (code "57") (name "Net-(LED1-PadSDO)") (class "Default")
      (node (ref "LED1") (pin "SDO") (pinfunction "SDO_SDO") (pintype "bidirectional"))
      (node (ref "SPI-LED") (pin "DI") (pinfunction "DI_DI") (pintype "bidirectional"))
    )
    (net (code "58") (name "Net-(Q3-PadD)") (class "Default")
      (node (ref "Q3") (pin "D") (pinfunction "D_D") (pintype "passive"))
      (node (ref "R26") (pin "2") (pinfunction "2_2") (pintype "bidirectional"))
    )
    (net (code "59") (name "Net-(Q3-PadG)") (class "Default")
      (node (ref "Q3") (pin "G") (pinfunction "G_G") (pintype "passive"))
      (node (ref "R24") (pin "1") (pinfunction "1_1") (pintype "bidirectional"))
      (node (ref "R8") (pin "1") (pinfunction "1_1") (pintype "bidirectional"))
    )
    (net (code "60") (name "Net-(Q4-PadD)") (class "Default")
      (node (ref "Q4") (pin "D") (pinfunction "D_D") (pintype "passive"))
      (node (ref "R27") (pin "2") (pinfunction "2_2") (pintype "bidirectional"))
    )
    (net (code "61") (name "Net-(Q4-PadG)") (class "Default")
      (node (ref "Q4") (pin "G") (pinfunction "G_G") (pintype "passive"))
      (node (ref "R33") (pin "1") (pinfunction "1_1") (pintype "bidirectional"))
      (node (ref "R35") (pin "2") (pinfunction "2_2") (pintype "bidirectional"))
    )
    (net (code "62") (name "Net-(Q5-PadD)") (class "Default")
      (node (ref "Q5") (pin "D") (pinfunction "D_D") (pintype "passive"))
      (node (ref "R29") (pin "2") (pinfunction "2_2") (pintype "bidirectional"))
    )
    (net (code "63") (name "Net-(Q5-PadG)") (class "Default")
      (node (ref "Q5") (pin "G") (pinfunction "G_G") (pintype "passive"))
      (node (ref "R32") (pin "1") (pinfunction "1_1") (pintype "bidirectional"))
      (node (ref "R34") (pin "2") (pinfunction "2_2") (pintype "bidirectional"))
    )
    (net (code "64") (name "Net-(R7-Pad2)") (class "Default")
      (node (ref "R7") (pin "2") (pinfunction "2_2") (pintype "bidirectional"))
      (node (ref "RCPWR") (pin "CATHODE") (pinfunction "CATHODE_CATHODE") (pintype "passive"))
    )
    (net (code "65") (name "Net-(U$1-11:SIGNAL_ST)") (class "Default")
      (node (ref "R20") (pin "2") (pinfunction "2_2") (pintype "bidirectional"))
      (node (ref "U$1") (pin "11:ST_SIGNAL") (pinfunction "11:SIGNAL_ST_11:ST_SIGNAL") (pintype "bidirectional"))
    )
    (net (code "66") (name "Net-(U$1-15:SIGNAL_TH)") (class "Default")
      (node (ref "R21") (pin "2") (pinfunction "2_2") (pintype "bidirectional"))
      (node (ref "U$1") (pin "15:TH_SINGNAL") (pinfunction "15:SIGNAL_TH_15:TH_SINGNAL") (pintype "bidirectional"))
    )
    (net (code "67") (name "Net-(U1-C)") (class "Default")
      (node (ref "R26") (pin "1") (pinfunction "1_1") (pintype "bidirectional"))
      (node (ref "U1") (pin "2") (pinfunction "C_2") (pintype "passive"))
    )
    (net (code "68") (name "Net-(U1-EMI)") (class "Default")
      (node (ref "R6") (pin "1") (pinfunction "1_1") (pintype "bidirectional"))
      (node (ref "U1") (pin "3") (pinfunction "EMI_3") (pintype "passive"))
      (node (ref "U2") (pin "P$17") (pinfunction "PA10_A2_D2_P$17") (pintype "bidirectional"))
      (node (ref "U2") (pin "P$3") (pinfunction "PA10_A2_D2_P$3") (pintype "bidirectional"))
    )
    (net (code "69") (name "Net-(U3-1:AN1)") (class "Default")
      (node (ref "R16") (pin "1") (pinfunction "1_1") (pintype "bidirectional"))
      (node (ref "U3") (pin "1") (pinfunction "1:AN1_1") (pintype "bidirectional"))
    )
    (net (code "70") (name "Net-(U3-2:CA1)") (class "Default")
      (node (ref "R29") (pin "1") (pinfunction "1_1") (pintype "bidirectional"))
      (node (ref "U3") (pin "2") (pinfunction "2:CA1_2") (pintype "bidirectional"))
    )
    (net (code "71") (name "Net-(U3-3:CA2)") (class "Default")
      (node (ref "R27") (pin "1") (pinfunction "1_1") (pintype "bidirectional"))
      (node (ref "U3") (pin "3") (pinfunction "3:CA2_3") (pintype "bidirectional"))
    )
    (net (code "72") (name "Net-(U3-4:AN2)") (class "Default")
      (node (ref "R15") (pin "1") (pinfunction "1_1") (pintype "bidirectional"))
      (node (ref "U3") (pin "4") (pinfunction "4:AN2_4") (pintype "bidirectional"))
    )
    (net (code "73") (name "Net-(U3-6:OUT2)") (class "Default")
      (node (ref "U2") (pin "P$16") (pinfunction "PA4_A1_D1_P$16") (pintype "bidirectional"))
      (node (ref "U2") (pin "P$2") (pinfunction "PA4_A1_D1_P$2") (pintype "bidirectional"))
      (node (ref "U3") (pin "6") (pinfunction "6:OUT2_6") (pintype "bidirectional"))
    )
    (net (code "74") (name "Net-(U3-7:OUT1)") (class "Default")
      (node (ref "U2") (pin "P$1") (pinfunction "PA02_A0_D0_P$1") (pintype "bidirectional"))
      (node (ref "U2") (pin "P$15") (pinfunction "PA02_A0_D0_P$15") (pintype "bidirectional"))
      (node (ref "U3") (pin "7") (pinfunction "7:OUT1_7") (pintype "bidirectional"))
    )
    (net (code "75") (name "Net-(U4-BS1)") (class "Default")
      (node (ref "R19") (pin "2") (pinfunction "2_2") (pintype "bidirectional"))
      (node (ref "U4") (pin "20") (pinfunction "BS1_20") (pintype "bidirectional"))
    )
    (net (code "76") (name "Net-(U4-C1N)") (class "Default")
      (node (ref "C19") (pin "1") (pinfunction "1_1") (pintype "passive"))
      (node (ref "U4") (pin "26") (pinfunction "C1N_26") (pintype "bidirectional"))
    )
    (net (code "77") (name "Net-(U4-C1P)") (class "Default")
      (node (ref "C19") (pin "2") (pinfunction "2_2") (pintype "passive"))
      (node (ref "U4") (pin "27") (pinfunction "C1P_27") (pintype "bidirectional"))
    )
    (net (code "78") (name "Net-(U4-C2N)") (class "Default")
      (node (ref "C22") (pin "1") (pinfunction "1_1") (pintype "passive"))
      (node (ref "U4") (pin "28") (pinfunction "C2N_28") (pintype "bidirectional"))
    )
    (net (code "79") (name "Net-(U4-C2P)") (class "Default")
      (node (ref "C22") (pin "2") (pinfunction "2_2") (pintype "passive"))
      (node (ref "U4") (pin "29") (pinfunction "C2P_29") (pintype "bidirectional"))
    )
    (net (code "80") (name "Net-(U4-D{slash}C#)") (class "Default")
      (node (ref "R36") (pin "2") (pinfunction "2_2") (pintype "bidirectional"))
      (node (ref "R37") (pin "1") (pinfunction "1_1") (pintype "bidirectional"))
      (node (ref "U4") (pin "16") (pinfunction "D/C#_16") (pintype "bidirectional"))
    )
    (net (code "81") (name "Net-(U4-IREF)") (class "Default")
      (node (ref "R13") (pin "1") (pinfunction "1_1") (pintype "bidirectional"))
      (node (ref "U4") (pin "5") (pinfunction "IREF_5") (pintype "bidirectional"))
    )
    (net (code "82") (name "Net-(U4-RES#)") (class "Default")
      (node (ref "R31") (pin "2") (pinfunction "2_2") (pintype "bidirectional"))
      (node (ref "U4") (pin "17") (pinfunction "RES#_17") (pintype "bidirectional"))
    )
    (net (code "83") (name "Net-(U4-VCC)") (class "Default")
      (node (ref "C13") (pin "2") (pinfunction "2_2") (pintype "passive"))
      (node (ref "U4") (pin "3") (pinfunction "VCC_3") (pintype "bidirectional"))
    )
    (net (code "84") (name "Net-(U4-VCOMH)") (class "Default")
      (node (ref "C16") (pin "2") (pinfunction "2_2") (pintype "passive"))
      (node (ref "U4") (pin "4") (pinfunction "VCOMH_4") (pintype "bidirectional"))
    )
    (net (code "85") (name "XIAO_5V") (class "Default")
      (node (ref "U2") (pin "P$14") (pinfunction "5V_P$14") (pintype "bidirectional"))
      (node (ref "U2") (pin "P$28") (pinfunction "5V_P$28") (pintype "bidirectional"))
    )
    (net (code "86") (name "unconnected-(IC3-A2-Pad11)") (class "Default")
      (node (ref "IC3") (pin "11") (pinfunction "A2_11") (pintype "bidirectional"))
    )
    (net (code "87") (name "unconnected-(IC3-A3-Pad14)") (class "Default")
      (node (ref "IC3") (pin "14") (pinfunction "A3_14") (pintype "bidirectional"))
    )
    (net (code "88") (name "unconnected-(IC3-B2-Pad10)") (class "Default")
      (node (ref "IC3") (pin "10") (pinfunction "B2_10") (pintype "bidirectional"))
    )
    (net (code "89") (name "unconnected-(IC3-B3-Pad13)") (class "Default")
      (node (ref "IC3") (pin "13") (pinfunction "B3_13") (pintype "bidirectional"))
    )
    (net (code "90") (name "unconnected-(IC3-Y2-Pad9)") (class "Default")
      (node (ref "IC3") (pin "9") (pinfunction "Y2_9") (pintype "bidirectional"))
    )
    (net (code "91") (name "unconnected-(IC3-Y3-Pad12)") (class "Default")
      (node (ref "IC3") (pin "12") (pinfunction "Y3_12") (pintype "bidirectional"))
    )
    (net (code "92") (name "unconnected-(IC4-LED2-Pad8)") (class "Default")
      (node (ref "IC4") (pin "8") (pinfunction "LED2_8") (pintype "bidirectional"))
    )
    (net (code "93") (name "unconnected-(IC4-LED3-Pad9)") (class "Default")
      (node (ref "IC4") (pin "9") (pinfunction "LED3_9") (pintype "bidirectional"))
    )
    (net (code "94") (name "unconnected-(IC4-LED4-Pad10)") (class "Default")
      (node (ref "IC4") (pin "10") (pinfunction "LED4_10") (pintype "bidirectional"))
    )
    (net (code "95") (name "unconnected-(IC4-LED5-Pad11)") (class "Default")
      (node (ref "IC4") (pin "11") (pinfunction "LED5_11") (pintype "bidirectional"))
    )
    (net (code "96") (name "unconnected-(IC4-LED6-Pad12)") (class "Default")
      (node (ref "IC4") (pin "12") (pinfunction "LED6_12") (pintype "bidirectional"))
    )
    (net (code "97") (name "unconnected-(IC4-LED7-Pad13)") (class "Default")
      (node (ref "IC4") (pin "13") (pinfunction "LED7_13") (pintype "bidirectional"))
    )
    (net (code "98") (name "unconnected-(IC4-LED8-Pad15)") (class "Default")
      (node (ref "IC4") (pin "15") (pinfunction "LED8_15") (pintype "bidirectional"))
    )
    (net (code "99") (name "unconnected-(IC4-LED9-Pad16)") (class "Default")
      (node (ref "IC4") (pin "16") (pinfunction "LED9_16") (pintype "bidirectional"))
    )
    (net (code "100") (name "unconnected-(IC4-LED10-Pad17)") (class "Default")
      (node (ref "IC4") (pin "17") (pinfunction "LED10_17") (pintype "bidirectional"))
    )
    (net (code "101") (name "unconnected-(IC4-LED11-Pad18)") (class "Default")
      (node (ref "IC4") (pin "18") (pinfunction "LED11_18") (pintype "bidirectional"))
    )
    (net (code "102") (name "unconnected-(IC4-LED12-Pad19)") (class "Default")
      (node (ref "IC4") (pin "19") (pinfunction "LED12_19") (pintype "bidirectional"))
    )
    (net (code "103") (name "unconnected-(IC4-LED13-Pad20)") (class "Default")
      (node (ref "IC4") (pin "20") (pinfunction "LED13_20") (pintype "bidirectional"))
    )
    (net (code "104") (name "unconnected-(IC4-LED14-Pad21)") (class "Default")
      (node (ref "IC4") (pin "21") (pinfunction "LED14_21") (pintype "bidirectional"))
    )
    (net (code "105") (name "unconnected-(IC4-LED15-Pad22)") (class "Default")
      (node (ref "IC4") (pin "22") (pinfunction "LED15_22") (pintype "bidirectional"))
    )
    (net (code "106") (name "unconnected-(U$9-CE1-Pad26)") (class "Default")
      (node (ref "U$9") (pin "26") (pinfunction "CE1_26") (pintype "bidirectional"))
    )
    (net (code "107") (name "unconnected-(U$9-ID_SC-Pad28)") (class "Default")
      (node (ref "U$9") (pin "28") (pinfunction "ID_SC_28") (pintype "bidirectional"))
    )
    (net (code "108") (name "unconnected-(U$9-ID_SD-Pad27)") (class "Default")
      (node (ref "U$9") (pin "27") (pinfunction "ID_SD_27") (pintype "bidirectional"))
    )
    (net (code "109") (name "unconnected-(U4-NC-Pad1)") (class "Default")
      (node (ref "U4") (pin "1") (pinfunction "NC_1") (pintype "bidirectional"))
    )
    (net (code "110") (name "unconnected-(U4-NC-Pad24)") (class "Default")
      (node (ref "U4") (pin "24") (pinfunction "NC_24") (pintype "bidirectional"))
    )
    (net (code "111") (name "unconnected-(U4-NC-Pad30)") (class "Default")
      (node (ref "U4") (pin "30") (pinfunction "NC_30") (pintype "bidirectional"))
    )
  )
)
